# Connectors.net
KiCad netlist of a schematic drawn in Altium Designer
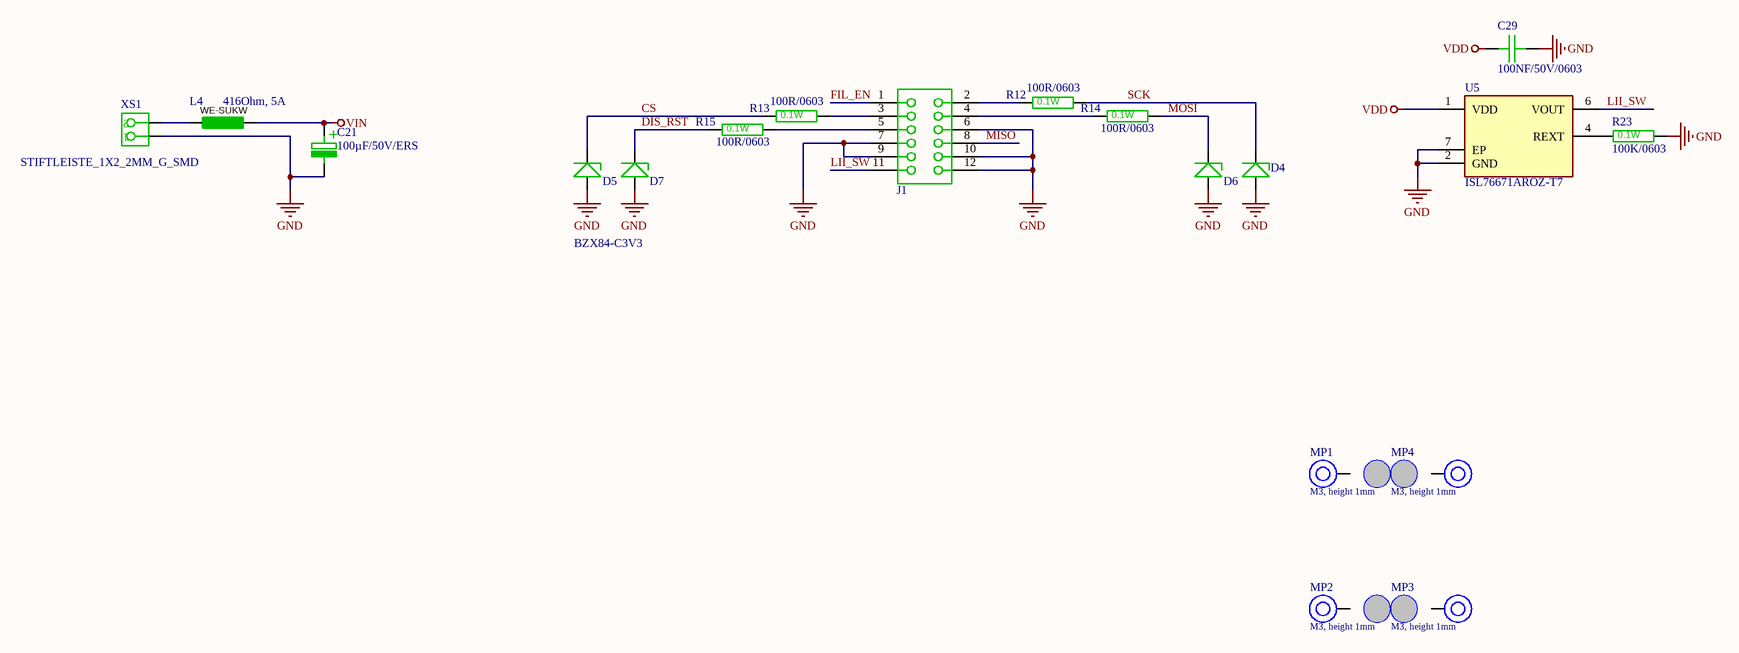
[diagram p0: Connectors.SchDoc]

(export (version "E")
  (design (tool "Eeschema 10.0.6"))
  (components
    (comp (ref "C21")
      (value "100µF/50V/ERS")
      (footprint "AL-ERS8x8__R")
      (description "Capacitor, 100µF, Low ESR, 105 °C, 50V, 20%, Al-Elektrolyt, SMD, Größe ERS8x8")
      (libsource (lib "SCH_SMD_Passive_Capacitor_Al") (part "100µF/50V/ERS"))
    )
    (comp (ref "C29")
      (value "100NF/50V/0603")
      (footprint "0603__R")
      (description "Capacitor, 100nF, 50V, 10%, Ceramic XR7, SMD, 0603")
      (fields
        (field (name "MANUFACTURER") "KEMET")
        (field (name "MANUFACTURER PART NUMBER") "C0603X104K5RACTU")
      )
      (libsource (lib "SCH_SMD_Passive_Capacitor_0603") (part "100NF/50V/0603"))
    )
    (comp (ref "D4")
      (value "BZX84-C3V3")
      (footprint "SOT-23-3__R")
      (description "DIODE ZENER 3.3V 250MW SOT23")
      (fields
        (field (name "MANUFACTURER") "Nexperia USA Inc.")
        (field (name "MANUFACTURER PART NUMBER") "BZX84-C3V3,215")
      )
      (libsource (lib "SCH_SMD_Active_Diode") (part "BZX84-C3V3"))
    )
    (comp (ref "D5")
      (value "BZX84-C3V3")
      (footprint "SOT-23-3__R")
      (description "DIODE ZENER 3.3V 250MW SOT23")
      (fields
        (field (name "MANUFACTURER") "Nexperia USA Inc.")
        (field (name "MANUFACTURER PART NUMBER") "BZX84-C3V3,215")
      )
      (libsource (lib "SCH_SMD_Active_Diode") (part "BZX84-C3V3"))
    )
    (comp (ref "D6")
      (value "BZX84-C3V3")
      (footprint "SOT-23-3__R")
      (description "DIODE ZENER 3.3V 250MW SOT23")
      (fields
        (field (name "MANUFACTURER") "Nexperia USA Inc.")
        (field (name "MANUFACTURER PART NUMBER") "BZX84-C3V3,215")
      )
      (libsource (lib "SCH_SMD_Active_Diode") (part "BZX84-C3V3"))
    )
    (comp (ref "D7")
      (value "BZX84-C3V3")
      (footprint "SOT-23-3__R")
      (description "DIODE ZENER 3.3V 250MW SOT23")
      (fields
        (field (name "MANUFACTURER") "Nexperia USA Inc.")
        (field (name "MANUFACTURER PART NUMBER") "BZX84-C3V3,215")
      )
      (libsource (lib "SCH_SMD_Active_Diode") (part "BZX84-C3V3"))
    )
    (comp (ref "J1")
      (value "490107671212")
      (footprint "490107671212_Permanent Application")
      (description "WR-WST REDFIT IDC SKEDD, pitch 2.54mm, 12p")
      (fields (field (name "MANUFACTURER") "Wurth Elektronik"))
      (libsource (lib "DAC") (part "490107671212"))
    )
    (comp (ref "L4")
      (value "416Ohm, 5A")
      (footprint "7427511_WE-SUKW__R")
      (description "WE-SUKW SMT EMI Suppression 5-Hole Ferrite Bead, , 416Ohm, 5A")
      (fields
        (field (name "MANUFACTURER PART NUMBER") "7427511")
        (field (name "MANUFACTURER") "Wurth Elektronik")
      )
      (libsource (lib "SCH_SMD_Passive_Wuerth") (part "7427511"))
    )
    (comp (ref "MP1")
      (value "M3, height 1mm")
      (footprint "9774010360_R")
      (description "SMT Steel Spacer with internal Thread M3 WA-SMSI, height 1mm")
      (fields
        (field (name "PART NUMBER") "9774010360")
        (field (name "MANUFACTURER") "Wurth Electronics")
        (field (name "PUBLISHER") "Wurth Elektronik")
      )
      (libsource (lib "") (part "9774010360_1"))
    )
    (comp (ref "MP2")
      (value "M3, height 1mm")
      (footprint "9774010360_R")
      (description "SMT Steel Spacer with internal Thread M3 WA-SMSI, height 1mm")
      (fields
        (field (name "PART NUMBER") "9774010360")
        (field (name "MANUFACTURER") "Wurth Electronics")
        (field (name "PUBLISHER") "Wurth Elektronik")
      )
      (libsource (lib "") (part "9774010360_1"))
    )
    (comp (ref "MP3")
      (value "M3, height 1mm")
      (footprint "9774010360_R")
      (description "SMT Steel Spacer with internal Thread M3 WA-SMSI, height 1mm")
      (fields
        (field (name "PART NUMBER") "9774010360")
        (field (name "MANUFACTURER") "Wurth Electronics")
        (field (name "PUBLISHER") "Wurth Elektronik")
      )
      (libsource (lib "SCH_Passive_Universal") (part "9774010360"))
    )
    (comp (ref "MP4")
      (value "M3, height 1mm")
      (footprint "9774010360_R")
      (description "SMT Steel Spacer with internal Thread M3 WA-SMSI, height 1mm")
      (fields
        (field (name "PART NUMBER") "9774010360")
        (field (name "MANUFACTURER") "Wurth Electronics")
        (field (name "PUBLISHER") "Wurth Elektronik")
      )
      (libsource (lib "SCH_Passive_Universal") (part "9774010360"))
    )
    (comp (ref "R12")
      (value "100R/0603")
      (footprint "0603__R")
      (description "Resistor, 100R, 0.1W, 1%, TK50, Metallschicht, SMD, 0603")
      (libsource (lib "SCH_SMD_Passive_Resistor_0603") (part "100R/0603"))
    )
    (comp (ref "R13")
      (value "100R/0603")
      (footprint "0603__R")
      (description "Resistor, 100R, 0.1W, 1%, TK50, Metallschicht, SMD, 0603")
      (libsource (lib "SCH_SMD_Passive_Resistor_0603") (part "100R/0603"))
    )
    (comp (ref "R14")
      (value "100R/0603")
      (footprint "0603__R")
      (description "Resistor, 100R, 0.1W, 1%, TK50, Metallschicht, SMD, 0603")
      (libsource (lib "SCH_SMD_Passive_Resistor_0603") (part "100R/0603"))
    )
    (comp (ref "R15")
      (value "100R/0603")
      (footprint "0603__R")
      (description "Resistor, 100R, 0.1W, 1%, TK50, Metallschicht, SMD, 0603")
      (libsource (lib "SCH_SMD_Passive_Resistor_0603") (part "100R/0603"))
    )
    (comp (ref "R23")
      (value "100K/0603")
      (footprint "0603__R")
      (description "Resistor, 100K, 0.1W, 1%, TK50, Metallschicht, SMD, 0603")
      (libsource (lib "GP1247AI_1") (part "100K/0603"))
    )
    (comp (ref "U5")
      (value "ISL76671AROZ-T7")
      (footprint "SON65P210X200X80-7N")
      (fields (field (name "MOUSER PART NUMBER") "968-ISL76671AROZ-T7"))
      (libsource (lib "GP1247AI_1") (part "ISL76671AROZ-T7"))
    )
    (comp (ref "XS1")
      (value "STIFTLEISTE_1X2_2MM_G_SMD")
      (footprint "1X2POL-2mm-G__R")
      (fields
        (field (name "MANUFACTURER") "JST Sales America Inc")
        (field (name "MANUFACTURER PART NUMBER") "B2B-PH-SM4-TB(LF)(SN)")
      )
      (libsource (lib "SCH_SMD_Connectors_JST_2mm") (part "STIFTLEISTE_1X2_2MM_G_SMD"))
    )
  )
  (nets
    (net (code "1") (name "/CS") (class "Default")
      (node (ref "D5") (pin "3") (pintype "passive"))
      (node (ref "R13") (pin "1") (pinfunction "1_1") (pintype "passive"))
    )
    (net (code "2") (name "/DIS_RST") (class "Default")
      (node (ref "D7") (pin "3") (pintype "passive"))
      (node (ref "R15") (pin "1") (pinfunction "1_1") (pintype "passive"))
    )
    (net (code "3") (name "/FIL_EN") (class "Default")
      (node (ref "J1") (pin "1") (pinfunction "1_1") (pintype "passive"))
    )
    (net (code "4") (name "/LII_SW") (class "Default")
      (node (ref "J1") (pin "11") (pinfunction "11_11") (pintype "passive"))
      (node (ref "U5") (pin "6") (pinfunction "VOUT_6") (pintype "passive"))
    )
    (net (code "5") (name "/MISO") (class "Default")
      (node (ref "J1") (pin "8") (pinfunction "8_8") (pintype "passive"))
    )
    (net (code "6") (name "/MOSI") (class "Default")
      (node (ref "D6") (pin "3") (pintype "passive"))
      (node (ref "R14") (pin "2") (pinfunction "2_2") (pintype "passive"))
    )
    (net (code "7") (name "/SCK") (class "Default")
      (node (ref "D4") (pin "3") (pintype "passive"))
      (node (ref "R12") (pin "2") (pinfunction "2_2") (pintype "passive"))
    )
    (net (code "8") (name "GND") (class "Default")
      (node (ref "C21") (pin "1") (pinfunction "1_1") (pintype "passive"))
      (node (ref "C29") (pin "1") (pinfunction "1_1") (pintype "passive"))
      (node (ref "D4") (pin "1") (pintype "passive"))
      (node (ref "D5") (pin "1") (pintype "passive"))
      (node (ref "D6") (pin "1") (pintype "passive"))
      (node (ref "D7") (pin "1") (pintype "passive"))
      (node (ref "J1") (pin "10") (pinfunction "10_10") (pintype "passive"))
      (node (ref "J1") (pin "12") (pinfunction "12_12") (pintype "passive"))
      (node (ref "J1") (pin "6") (pinfunction "6_6") (pintype "passive"))
      (node (ref "J1") (pin "7") (pinfunction "7_7") (pintype "passive"))
      (node (ref "J1") (pin "9") (pinfunction "9_9") (pintype "passive"))
      (node (ref "R23") (pin "2") (pinfunction "2_2") (pintype "passive"))
      (node (ref "U5") (pin "2") (pinfunction "GND_2") (pintype "passive"))
      (node (ref "U5") (pin "7") (pinfunction "EP_7") (pintype "passive"))
      (node (ref "XS1") (pin "1") (pinfunction "1_1") (pintype "passive"))
    )
    (net (code "9") (name "Net-(J1-Pad2)") (class "Default")
      (node (ref "J1") (pin "2") (pinfunction "2_2") (pintype "passive"))
      (node (ref "R12") (pin "1") (pinfunction "1_1") (pintype "passive"))
    )
    (net (code "10") (name "Net-(J1-Pad3)") (class "Default")
      (node (ref "J1") (pin "3") (pinfunction "3_3") (pintype "passive"))
      (node (ref "R13") (pin "2") (pinfunction "2_2") (pintype "passive"))
    )
    (net (code "11") (name "Net-(J1-Pad4)") (class "Default")
      (node (ref "J1") (pin "4") (pinfunction "4_4") (pintype "passive"))
      (node (ref "R14") (pin "1") (pinfunction "1_1") (pintype "passive"))
    )
    (net (code "12") (name "Net-(J1-Pad5)") (class "Default")
      (node (ref "J1") (pin "5") (pinfunction "5_5") (pintype "passive"))
      (node (ref "R15") (pin "2") (pinfunction "2_2") (pintype "passive"))
    )
    (net (code "13") (name "Net-(L4-Pad1)") (class "Default")
      (node (ref "L4") (pin "1") (pinfunction "1_1") (pintype "passive"))
      (node (ref "XS1") (pin "2") (pinfunction "2_2") (pintype "passive"))
    )
    (net (code "14") (name "Net-(U5-REXT)") (class "Default")
      (node (ref "R23") (pin "1") (pinfunction "1_1") (pintype "passive"))
      (node (ref "U5") (pin "4") (pinfunction "REXT_4") (pintype "passive"))
    )
    (net (code "15") (name "VDD") (class "Default")
      (node (ref "C29") (pin "2") (pinfunction "2_2") (pintype "passive"))
      (node (ref "U5") (pin "1") (pinfunction "VDD_1") (pintype "passive"))
    )
    (net (code "16") (name "VIN") (class "Default")
      (node (ref "C21") (pin "2") (pinfunction "2_2") (pintype "passive"))
      (node (ref "L4") (pin "2") (pinfunction "2_2") (pintype "passive"))
    )
    (net (code "17") (name "unconnected-(MP1-Pad1)") (class "Default")
      (node (ref "MP1") (pin "1") (pinfunction "1_1") (pintype "passive"))
    )
    (net (code "18") (name "unconnected-(MP2-Pad1)") (class "Default")
      (node (ref "MP2") (pin "1") (pinfunction "1_1") (pintype "passive"))
    )
    (net (code "19") (name "unconnected-(MP3-Pad1)") (class "Default")
      (node (ref "MP3") (pin "1") (pinfunction "1_1") (pintype "passive"))
    )
    (net (code "20") (name "unconnected-(MP4-Pad1)") (class "Default")
      (node (ref "MP4") (pin "1") (pinfunction "1_1") (pintype "passive"))
    )
    (net (code "21") (name "unconnected-(U5-NC_1-Pad3)") (class "Default")
      (node (ref "U5") (pin "3") (pinfunction "NC_1_3") (pintype "passive"))
    )
    (net (code "22") (name "unconnected-(U5-NC_2-Pad5)") (class "Default")
      (node (ref "U5") (pin "5") (pinfunction "NC_2_5") (pintype "passive"))
    )
  )
)
